# BSPD.net
KiCad netlist of a schematic drawn in EAGLE
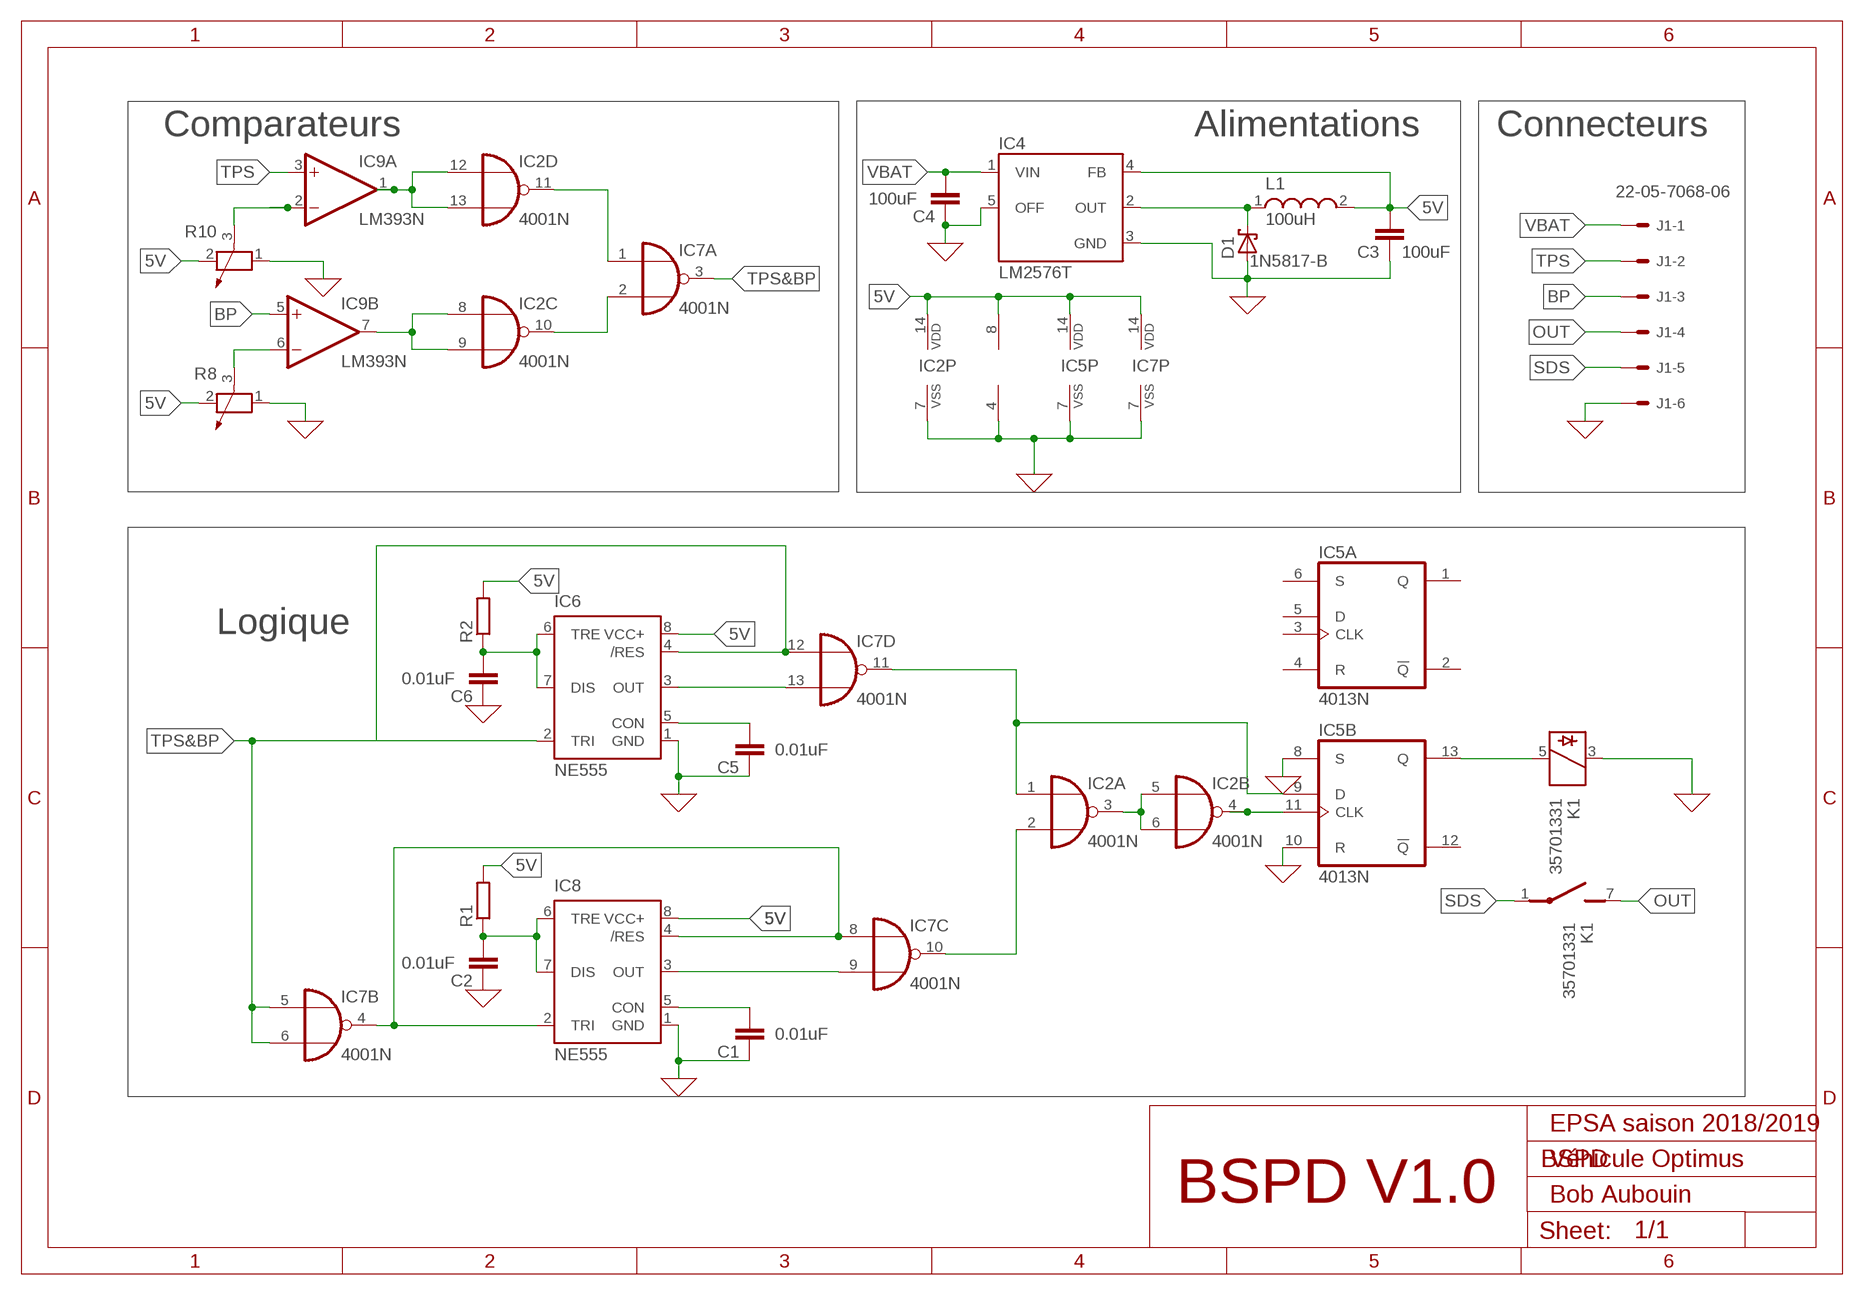
[diagram p0: schematic, sheet 1]

(export (version "E")
  (design (tool "Eeschema 10.0.6"))
  (components
    (comp (ref "C1")
      (value "0.01uF")
      (footprint "eagle-import:C025-025X050")
      (libsource (lib "eagle-import") (part "C-EU025-025X050"))
    )
    (comp (ref "C2")
      (value "0.01uF")
      (footprint "eagle-import:C025-025X050")
      (libsource (lib "eagle-import") (part "C-EU025-025X050"))
    )
    (comp (ref "C3")
      (value "100uF")
      (footprint "eagle-import:C025-025X050")
      (libsource (lib "eagle-import") (part "C-EU025-025X050"))
    )
    (comp (ref "C4")
      (value "100uF")
      (footprint "eagle-import:C025-025X050")
      (libsource (lib "eagle-import") (part "C-EU025-025X050"))
    )
    (comp (ref "C5")
      (value "0.01uF")
      (footprint "eagle-import:C025-025X050")
      (libsource (lib "eagle-import") (part "C-EU025-025X050"))
    )
    (comp (ref "C6")
      (value "0.01uF")
      (footprint "eagle-import:C025-025X050")
      (libsource (lib "eagle-import") (part "C-EU025-025X050"))
    )
    (comp (ref "D1")
      (value "1N5817-B")
      (footprint "eagle-import:DO41-7.6")
      (libsource (lib "eagle-import") (part "1N5817-B"))
    )
    (comp (ref "IC2")
      (value "4001N")
      (footprint "eagle-import:DIL14")
      (libsource (lib "eagle-import") (part "4001N"))
    )
    (comp (ref "IC4")
      (value "LM2576T")
      (footprint "eagle-import:TO220-5")
      (libsource (lib "eagle-import") (part "LM2576T"))
    )
    (comp (ref "IC5")
      (value "4013N")
      (footprint "eagle-import:DIL14")
      (libsource (lib "eagle-import") (part "4013N"))
    )
    (comp (ref "IC6")
      (value "NE555")
      (footprint "eagle-import:DIL-08")
      (fields (field (name "MF") "Arrow Electronics") (field (name "MPN") "NE555N"))
      (libsource (lib "eagle-import") (part "NE555"))
    )
    (comp (ref "IC7")
      (value "4001N")
      (footprint "eagle-import:DIL14")
      (libsource (lib "eagle-import") (part "4001N"))
    )
    (comp (ref "IC8")
      (value "NE555")
      (footprint "eagle-import:DIL-08")
      (fields (field (name "MF") "Arrow Electronics") (field (name "MPN") "NE555N"))
      (libsource (lib "eagle-import") (part "NE555"))
    )
    (comp (ref "IC9")
      (value "LM393N")
      (footprint "eagle-import:DIL08")
      (libsource (lib "eagle-import") (part "LM393N"))
    )
    (comp (ref "J1")
      (value "22-05-7068-06")
      (footprint "eagle-import:7395-06")
      (fields (field (name "MF") "MOLEX"))
      (libsource (lib "eagle-import") (part "22-?-0605-7068"))
    )
    (comp (ref "K1")
      (value "35701331")
      (footprint "eagle-import:REED")
      (libsource (lib "eagle-import") (part "35701331"))
    )
    (comp (ref "L1")
      (value "100uH")
      (footprint "eagle-import:WE-TI_8012")
      (libsource (lib "eagle-import") (part "WE-TI_8012"))
    )
    (comp (ref "R1")
      (value "R-EU_0207/10")
      (footprint "eagle-import:0207_10")
      (libsource (lib "eagle-import") (part "R-EU_0207/10"))
    )
    (comp (ref "R2")
      (value "R-EU_0207/10")
      (footprint "eagle-import:0207_10")
      (libsource (lib "eagle-import") (part "R-EU_0207/10"))
    )
    (comp (ref "R8")
      (value "POTENTIOMETER_PT_SPIN")
      (footprint "eagle-import:PT-SPIN")
      (libsource (lib "eagle-import") (part "POTENTIOMETER_PT_SPIN"))
    )
    (comp (ref "R10")
      (value "POTENTIOMETER_PT_SPIN")
      (footprint "eagle-import:PT-SPIN")
      (libsource (lib "eagle-import") (part "POTENTIOMETER_PT_SPIN"))
    )
  )
  (nets
    (net (code "1") (name "5V") (class "Default")
      (node (ref "C3") (pin "2") (pinfunction "2_2") (pintype "passive"))
      (node (ref "IC2") (pin "14") (pinfunction "VDD_14") (pintype "power_in"))
      (node (ref "IC4") (pin "4") (pinfunction "FB_4") (pintype "input"))
      (node (ref "IC5") (pin "14") (pinfunction "VDD_14") (pintype "power_in"))
      (node (ref "IC6") (pin "8") (pinfunction "VCC+_8") (pintype "power_in"))
      (node (ref "IC7") (pin "14") (pinfunction "VDD_14") (pintype "power_in"))
      (node (ref "IC8") (pin "8") (pinfunction "VCC+_8") (pintype "power_in"))
      (node (ref "IC9") (pin "8") (pinfunction "V+_8") (pintype "power_in"))
      (node (ref "L1") (pin "2") (pinfunction "2_2") (pintype "passive"))
      (node (ref "R1") (pin "2") (pinfunction "2_2") (pintype "passive"))
      (node (ref "R10") (pin "2") (pinfunction "2_2") (pintype "passive"))
      (node (ref "R2") (pin "2") (pinfunction "2_2") (pintype "passive"))
      (node (ref "R8") (pin "2") (pinfunction "2_2") (pintype "passive"))
    )
    (net (code "2") (name "BP") (class "Default")
      (node (ref "IC9") (pin "5") (pinfunction "+IN_5") (pintype "input"))
      (node (ref "J1") (pin "3") (pinfunction "S_3") (pintype "passive"))
    )
    (net (code "3") (name "GND") (class "Default")
      (node (ref "C1") (pin "1") (pinfunction "1_1") (pintype "passive"))
      (node (ref "C2") (pin "1") (pinfunction "1_1") (pintype "passive"))
      (node (ref "C3") (pin "1") (pinfunction "1_1") (pintype "passive"))
      (node (ref "C4") (pin "1") (pinfunction "1_1") (pintype "passive"))
      (node (ref "C5") (pin "1") (pinfunction "1_1") (pintype "passive"))
      (node (ref "C6") (pin "1") (pinfunction "1_1") (pintype "passive"))
      (node (ref "D1") (pin "A") (pinfunction "A_A") (pintype "passive"))
      (node (ref "IC2") (pin "7") (pinfunction "VSS_7") (pintype "power_in"))
      (node (ref "IC4") (pin "3") (pinfunction "GND_3") (pintype "power_in"))
      (node (ref "IC4") (pin "5") (pinfunction "OFF_5") (pintype "input"))
      (node (ref "IC5") (pin "10") (pinfunction "R_10") (pintype "input"))
      (node (ref "IC5") (pin "7") (pinfunction "VSS_7") (pintype "power_in"))
      (node (ref "IC5") (pin "8") (pinfunction "S_8") (pintype "input"))
      (node (ref "IC6") (pin "1") (pinfunction "GND_1") (pintype "power_in"))
      (node (ref "IC7") (pin "7") (pinfunction "VSS_7") (pintype "power_in"))
      (node (ref "IC8") (pin "1") (pinfunction "GND_1") (pintype "power_in"))
      (node (ref "IC9") (pin "4") (pinfunction "V-_4") (pintype "power_in"))
      (node (ref "J1") (pin "6") (pinfunction "S_6") (pintype "passive"))
      (node (ref "K1") (pin "3") (pinfunction "3_3") (pintype "passive"))
      (node (ref "R10") (pin "1") (pinfunction "1_1") (pintype "passive"))
      (node (ref "R8") (pin "1") (pinfunction "1_1") (pintype "passive"))
    )
    (net (code "4") (name "Net-(IC2A-I0)") (class "Default")
      (node (ref "IC2") (pin "1") (pinfunction "I0_1") (pintype "input"))
      (node (ref "IC5") (pin "9") (pinfunction "D_9") (pintype "input"))
      (node (ref "IC7") (pin "11") (pinfunction "O_11") (pintype "output"))
    )
    (net (code "5") (name "Net-(IC2A-I1)") (class "Default")
      (node (ref "IC2") (pin "2") (pinfunction "I1_2") (pintype "input"))
      (node (ref "IC7") (pin "10") (pinfunction "O_10") (pintype "output"))
    )
    (net (code "6") (name "Net-(IC2A-O)") (class "Default")
      (node (ref "IC2") (pin "3") (pinfunction "O_3") (pintype "output"))
      (node (ref "IC2") (pin "5") (pinfunction "I0_5") (pintype "input"))
      (node (ref "IC2") (pin "6") (pinfunction "I1_6") (pintype "input"))
    )
    (net (code "7") (name "Net-(IC2B-O)") (class "Default")
      (node (ref "IC2") (pin "4") (pinfunction "O_4") (pintype "output"))
      (node (ref "IC5") (pin "11") (pinfunction "CLK_11") (pintype "input"))
    )
    (net (code "8") (name "Net-(IC2C-I0)") (class "Default")
      (node (ref "IC2") (pin "8") (pinfunction "I0_8") (pintype "input"))
      (node (ref "IC2") (pin "9") (pinfunction "I1_9") (pintype "input"))
      (node (ref "IC9") (pin "7") (pinfunction "OUT_7") (pintype "output"))
    )
    (net (code "9") (name "Net-(IC2C-O)") (class "Default")
      (node (ref "IC2") (pin "10") (pinfunction "O_10") (pintype "output"))
      (node (ref "IC7") (pin "2") (pinfunction "I1_2") (pintype "input"))
    )
    (net (code "10") (name "Net-(IC2D-I0)") (class "Default")
      (node (ref "IC2") (pin "12") (pinfunction "I0_12") (pintype "input"))
      (node (ref "IC2") (pin "13") (pinfunction "I1_13") (pintype "input"))
      (node (ref "IC9") (pin "1") (pinfunction "OUT_1") (pintype "output"))
    )
    (net (code "11") (name "Net-(IC2D-O)") (class "Default")
      (node (ref "IC2") (pin "11") (pinfunction "O_11") (pintype "output"))
      (node (ref "IC7") (pin "1") (pinfunction "I0_1") (pintype "input"))
    )
    (net (code "12") (name "Net-(IC4-OUT)") (class "Default")
      (node (ref "D1") (pin "C") (pinfunction "C_C") (pintype "passive"))
      (node (ref "IC4") (pin "2") (pinfunction "OUT_2") (pintype "output"))
      (node (ref "L1") (pin "1") (pinfunction "1_1") (pintype "passive"))
    )
    (net (code "13") (name "Net-(IC5B-Q)") (class "Default")
      (node (ref "IC5") (pin "13") (pinfunction "Q_13") (pintype "output"))
      (node (ref "K1") (pin "5") (pinfunction "5_5") (pintype "passive"))
    )
    (net (code "14") (name "Net-(IC6-CON)") (class "Default")
      (node (ref "C5") (pin "2") (pinfunction "2_2") (pintype "passive"))
      (node (ref "IC6") (pin "5") (pinfunction "CON_5") (pintype "input"))
    )
    (net (code "15") (name "Net-(IC6-DIS)") (class "Default")
      (node (ref "C6") (pin "2") (pinfunction "2_2") (pintype "passive"))
      (node (ref "IC6") (pin "6") (pinfunction "TRE_6") (pintype "input"))
      (node (ref "IC6") (pin "7") (pinfunction "DIS_7") (pintype "input"))
      (node (ref "R2") (pin "1") (pinfunction "1_1") (pintype "passive"))
    )
    (net (code "16") (name "Net-(IC6-OUT)") (class "Default")
      (node (ref "IC6") (pin "3") (pinfunction "OUT_3") (pintype "output"))
      (node (ref "IC7") (pin "13") (pinfunction "I1_13") (pintype "input"))
    )
    (net (code "17") (name "Net-(IC7B-O)") (class "Default")
      (node (ref "IC7") (pin "4") (pinfunction "O_4") (pintype "output"))
      (node (ref "IC7") (pin "8") (pinfunction "I0_8") (pintype "input"))
      (node (ref "IC8") (pin "2") (pinfunction "TRI_2") (pintype "input"))
      (node (ref "IC8") (pin "4") (pinfunction "/RES_4") (pintype "input"))
    )
    (net (code "18") (name "Net-(IC7C-I1)") (class "Default")
      (node (ref "IC7") (pin "9") (pinfunction "I1_9") (pintype "input"))
      (node (ref "IC8") (pin "3") (pinfunction "OUT_3") (pintype "output"))
    )
    (net (code "19") (name "Net-(IC8-CON)") (class "Default")
      (node (ref "C1") (pin "2") (pinfunction "2_2") (pintype "passive"))
      (node (ref "IC8") (pin "5") (pinfunction "CON_5") (pintype "input"))
    )
    (net (code "20") (name "Net-(IC8-DIS)") (class "Default")
      (node (ref "C2") (pin "2") (pinfunction "2_2") (pintype "passive"))
      (node (ref "IC8") (pin "6") (pinfunction "TRE_6") (pintype "input"))
      (node (ref "IC8") (pin "7") (pinfunction "DIS_7") (pintype "input"))
      (node (ref "R1") (pin "1") (pinfunction "1_1") (pintype "passive"))
    )
    (net (code "21") (name "Net-(IC9A--IN)") (class "Default")
      (node (ref "IC9") (pin "2") (pinfunction "-IN_2") (pintype "input"))
      (node (ref "R10") (pin "3") (pinfunction "3_3") (pintype "passive"))
    )
    (net (code "22") (name "Net-(IC9B--IN)") (class "Default")
      (node (ref "IC9") (pin "6") (pinfunction "-IN_6") (pintype "input"))
      (node (ref "R8") (pin "3") (pinfunction "3_3") (pintype "passive"))
    )
    (net (code "23") (name "OUT") (class "Default")
      (node (ref "J1") (pin "4") (pinfunction "S_4") (pintype "passive"))
      (node (ref "K1") (pin "7") (pinfunction "S_7") (pintype "passive"))
    )
    (net (code "24") (name "SDS") (class "Default")
      (node (ref "J1") (pin "5") (pinfunction "S_5") (pintype "passive"))
      (node (ref "K1") (pin "1") (pinfunction "P_1") (pintype "passive"))
    )
    (net (code "25") (name "TPS") (class "Default")
      (node (ref "IC9") (pin "3") (pinfunction "+IN_3") (pintype "input"))
      (node (ref "J1") (pin "2") (pinfunction "S_2") (pintype "passive"))
    )
    (net (code "26") (name "TPS&BP") (class "Default")
      (node (ref "IC6") (pin "2") (pinfunction "TRI_2") (pintype "input"))
      (node (ref "IC6") (pin "4") (pinfunction "/RES_4") (pintype "input"))
      (node (ref "IC7") (pin "12") (pinfunction "I0_12") (pintype "input"))
      (node (ref "IC7") (pin "3") (pinfunction "O_3") (pintype "output"))
      (node (ref "IC7") (pin "5") (pinfunction "I0_5") (pintype "input"))
      (node (ref "IC7") (pin "6") (pinfunction "I1_6") (pintype "input"))
    )
    (net (code "27") (name "VBAT") (class "Default")
      (node (ref "C4") (pin "2") (pinfunction "2_2") (pintype "passive"))
      (node (ref "IC4") (pin "1") (pinfunction "VIN_1") (pintype "power_in"))
      (node (ref "J1") (pin "1") (pinfunction "S_1") (pintype "passive"))
    )
    (net (code "28") (name "unconnected-(IC5A-CLK-Pad3)") (class "Default")
      (node (ref "IC5") (pin "3") (pinfunction "CLK_3") (pintype "input"))
    )
    (net (code "29") (name "unconnected-(IC5A-D-Pad5)") (class "Default")
      (node (ref "IC5") (pin "5") (pinfunction "D_5") (pintype "input"))
    )
    (net (code "30") (name "unconnected-(IC5A-Q-Pad1)") (class "Default")
      (node (ref "IC5") (pin "1") (pinfunction "Q_1") (pintype "output"))
    )
    (net (code "31") (name "unconnected-(IC5A-R-Pad4)") (class "Default")
      (node (ref "IC5") (pin "4") (pinfunction "R_4") (pintype "input"))
    )
    (net (code "32") (name "unconnected-(IC5A-S-Pad6)") (class "Default")
      (node (ref "IC5") (pin "6") (pinfunction "S_6") (pintype "input"))
    )
    (net (code "33") (name "unconnected-(IC5A-~{Q}-Pad2)") (class "Default")
      (node (ref "IC5") (pin "2") (pinfunction "~{Q}_2") (pintype "output"))
    )
    (net (code "34") (name "unconnected-(IC5B-~{Q}-Pad12)") (class "Default")
      (node (ref "IC5") (pin "12") (pinfunction "~{Q}_12") (pintype "output"))
    )
  )
)
